# POWER_SUPPLY.net
KiCad netlist of a schematic drawn in Altium Designer
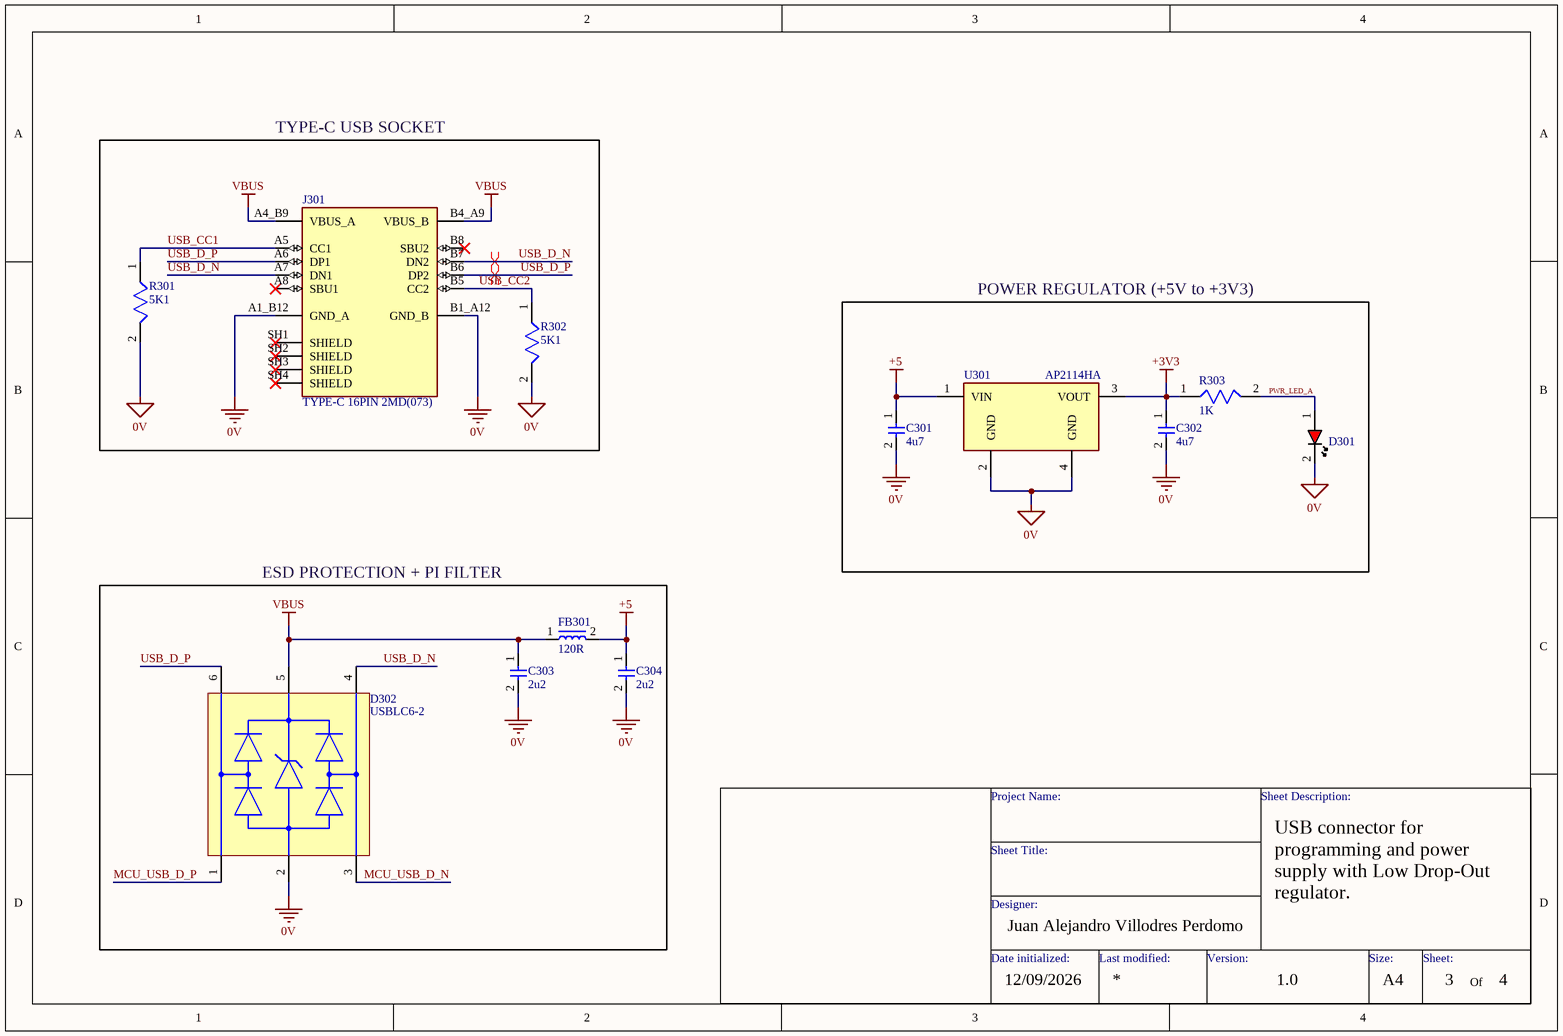
[diagram p0: POWER SUPPLY.SchDoc]

(export (version "E")
  (design (tool "Eeschema 10.0.6"))
  (components
    (comp (ref "C301")
      (value "4u7")
      (footprint "CAPC1608X90N")
      (description "Capacitor SMD 0603 16V")
      (libsource (lib "Integrated-Lib-JVillodres") (part "CAP_0603_16V"))
    )
    (comp (ref "C302")
      (value "4u7")
      (footprint "CAPC1608X90N")
      (description "Capacitor SMD 0603 16V")
      (libsource (lib "Integrated-Lib-JVillodres") (part "CAP_0603_16V"))
    )
    (comp (ref "C303")
      (value "2u2")
      (footprint "CAPC1608X90N")
      (description "Capacitor SMD 0603 16V")
      (libsource (lib "Integrated-Lib-JVillodres") (part "CAP_0603_16V"))
    )
    (comp (ref "C304")
      (value "2u2")
      (footprint "CAPC1608X90N")
      (description "Capacitor SMD 0603 16V")
      (libsource (lib "Integrated-Lib-JVillodres") (part "CAP_0603_16V"))
    )
    (comp (ref "D301")
      (value "LED_0402_RED")
      (footprint "LEDC0402")
      (description "LED RED SMD 0402")
      (libsource (lib "Integrated-Lib-JVillodres") (part "LED_0402_RED"))
    )
    (comp (ref "D302")
      (value "USBLC6-2")
      (footprint "SOT95P280X145-6N")
      (libsource (lib "Integrated-Lib-JVillodres") (part "USBLC6-2"))
    )
    (comp (ref "FB301")
      (value "120R")
      (footprint "FBC1608X95N")
      (description "Ferrite Bead SMD 0603")
      (libsource (lib "Integrated-Lib-JVillodres") (part "FB_0603"))
    )
    (comp (ref "J301")
      (value "TYPE-C 16PIN 2MD(073)")
      (footprint "SHOUHAN_TYPE-C_16PIN_2MD_(073)")
      (description "DC-5V 5A Type C USB")
      (libsource (lib "Integrated-Lib-JVillodres") (part "TYPE-C 16PIN 2MD(073)"))
    )
    (comp (ref "R301")
      (value "5K1")
      (footprint "RESC1005X37N")
      (description "Resistor SMD 0402")
      (libsource (lib "Integrated-Lib-JVillodres") (part "RES_0402"))
    )
    (comp (ref "R302")
      (value "5K1")
      (footprint "RESC1005X37N")
      (description "Resistor SMD 0402")
      (libsource (lib "Integrated-Lib-JVillodres") (part "RES_0402"))
    )
    (comp (ref "R303")
      (value "1K")
      (footprint "RESC1005X37N")
      (description "Resistor SMD 0402")
      (libsource (lib "Integrated-Lib-JVillodres") (part "RES_0402"))
    )
    (comp (ref "U301")
      (value "AP2114HA")
      (footprint "SOT230P700X180-4N")
      (libsource (lib "Integrated-Lib-JVillodres") (part "AP2114HA-3.3TRG1"))
    )
  )
  (nets
    (net (code "1") (name "+3V3") (class "Default")
      (node (ref "C302") (pin "1") (pintype "passive"))
      (node (ref "R303") (pin "1") (pintype "passive"))
      (node (ref "U301") (pin "3") (pinfunction "VOUT_3") (pintype "power_in"))
    )
    (net (code "2") (name "+5") (class "Default")
      (node (ref "C301") (pin "1") (pintype "passive"))
      (node (ref "C304") (pin "1") (pintype "passive"))
      (node (ref "FB301") (pin "2") (pinfunction "2_2") (pintype "passive"))
      (node (ref "U301") (pin "1") (pinfunction "VIN_1") (pintype "power_in"))
    )
    (net (code "3") (name "/MCU_USB_D_N") (class "Default")
      (node (ref "D302") (pin "3") (pinfunction "I/O2_3") (pintype "passive"))
    )
    (net (code "4") (name "/MCU_USB_D_P") (class "Default")
      (node (ref "D302") (pin "1") (pinfunction "I/O1_1") (pintype "passive"))
    )
    (net (code "5") (name "/PWR_LED_A") (class "Default")
      (node (ref "D301") (pin "1") (pinfunction "A_1") (pintype "passive"))
      (node (ref "R303") (pin "2") (pintype "passive"))
    )
    (net (code "6") (name "/USB_CC1") (class "Default")
      (node (ref "J301") (pin "A5") (pinfunction "CC1_A5") (pintype "bidirectional"))
      (node (ref "R301") (pin "1") (pintype "passive"))
    )
    (net (code "7") (name "/USB_CC2") (class "Default")
      (node (ref "J301") (pin "B5") (pinfunction "CC2_B5") (pintype "bidirectional"))
      (node (ref "R302") (pin "1") (pintype "passive"))
    )
    (net (code "8") (name "/USB_D_N") (class "Default")
      (node (ref "D302") (pin "4") (pinfunction "I/O2_4") (pintype "passive"))
      (node (ref "J301") (pin "A7") (pinfunction "DN1_A7") (pintype "bidirectional"))
      (node (ref "J301") (pin "B7") (pinfunction "DN2_B7") (pintype "bidirectional"))
    )
    (net (code "9") (name "/USB_D_P") (class "Default")
      (node (ref "D302") (pin "6") (pinfunction "I/O1_6") (pintype "passive"))
      (node (ref "J301") (pin "A6") (pinfunction "DP1_A6") (pintype "bidirectional"))
      (node (ref "J301") (pin "B6") (pinfunction "DP2_B6") (pintype "bidirectional"))
    )
    (net (code "10") (name "0V") (class "Default")
      (node (ref "C301") (pin "2") (pintype "passive"))
      (node (ref "C302") (pin "2") (pintype "passive"))
      (node (ref "C303") (pin "2") (pintype "passive"))
      (node (ref "C304") (pin "2") (pintype "passive"))
      (node (ref "D301") (pin "2") (pinfunction "K_2") (pintype "passive"))
      (node (ref "D302") (pin "2") (pinfunction "GND_2") (pintype "passive"))
      (node (ref "J301") (pin "A1_B12") (pinfunction "GND_A_A1_B12") (pintype "power_in"))
      (node (ref "J301") (pin "B1_A12") (pinfunction "GND_B_B1_A12") (pintype "power_in"))
      (node (ref "R301") (pin "2") (pintype "passive"))
      (node (ref "R302") (pin "2") (pintype "passive"))
      (node (ref "U301") (pin "2") (pinfunction "GND_2") (pintype "power_in"))
      (node (ref "U301") (pin "4") (pinfunction "GND_4") (pintype "power_in"))
    )
    (net (code "11") (name "VBUS") (class "Default")
      (node (ref "C303") (pin "1") (pintype "passive"))
      (node (ref "D302") (pin "5") (pinfunction "VBUS_5") (pintype "passive"))
      (node (ref "FB301") (pin "1") (pinfunction "1_1") (pintype "passive"))
      (node (ref "J301") (pin "A4_B9") (pinfunction "VBUS_A_A4_B9") (pintype "power_in"))
      (node (ref "J301") (pin "B4_A9") (pinfunction "VBUS_B_B4_A9") (pintype "power_in"))
    )
    (net (code "12") (name "unconnected-(J301-SBU1-PadA8)") (class "Default")
      (node (ref "J301") (pin "A8") (pinfunction "SBU1_A8") (pintype "bidirectional+no_connect"))
    )
    (net (code "13") (name "unconnected-(J301-SBU2-PadB8)") (class "Default")
      (node (ref "J301") (pin "B8") (pinfunction "SBU2_B8") (pintype "bidirectional+no_connect"))
    )
    (net (code "14") (name "unconnected-(J301-SHIELD-PadSH1)") (class "Default")
      (node (ref "J301") (pin "SH1") (pinfunction "SHIELD_SH1") (pintype "passive+no_connect"))
    )
    (net (code "15") (name "unconnected-(J301-SHIELD-PadSH2)") (class "Default")
      (node (ref "J301") (pin "SH2") (pinfunction "SHIELD_SH2") (pintype "passive+no_connect"))
    )
    (net (code "16") (name "unconnected-(J301-SHIELD-PadSH3)") (class "Default")
      (node (ref "J301") (pin "SH3") (pinfunction "SHIELD_SH3") (pintype "passive+no_connect"))
    )
    (net (code "17") (name "unconnected-(J301-SHIELD-PadSH4)") (class "Default")
      (node (ref "J301") (pin "SH4") (pinfunction "SHIELD_SH4") (pintype "passive+no_connect"))
    )
  )
)
